# RodManipulator_SCH.net
KiCad netlist of a schematic drawn in Altium Designer
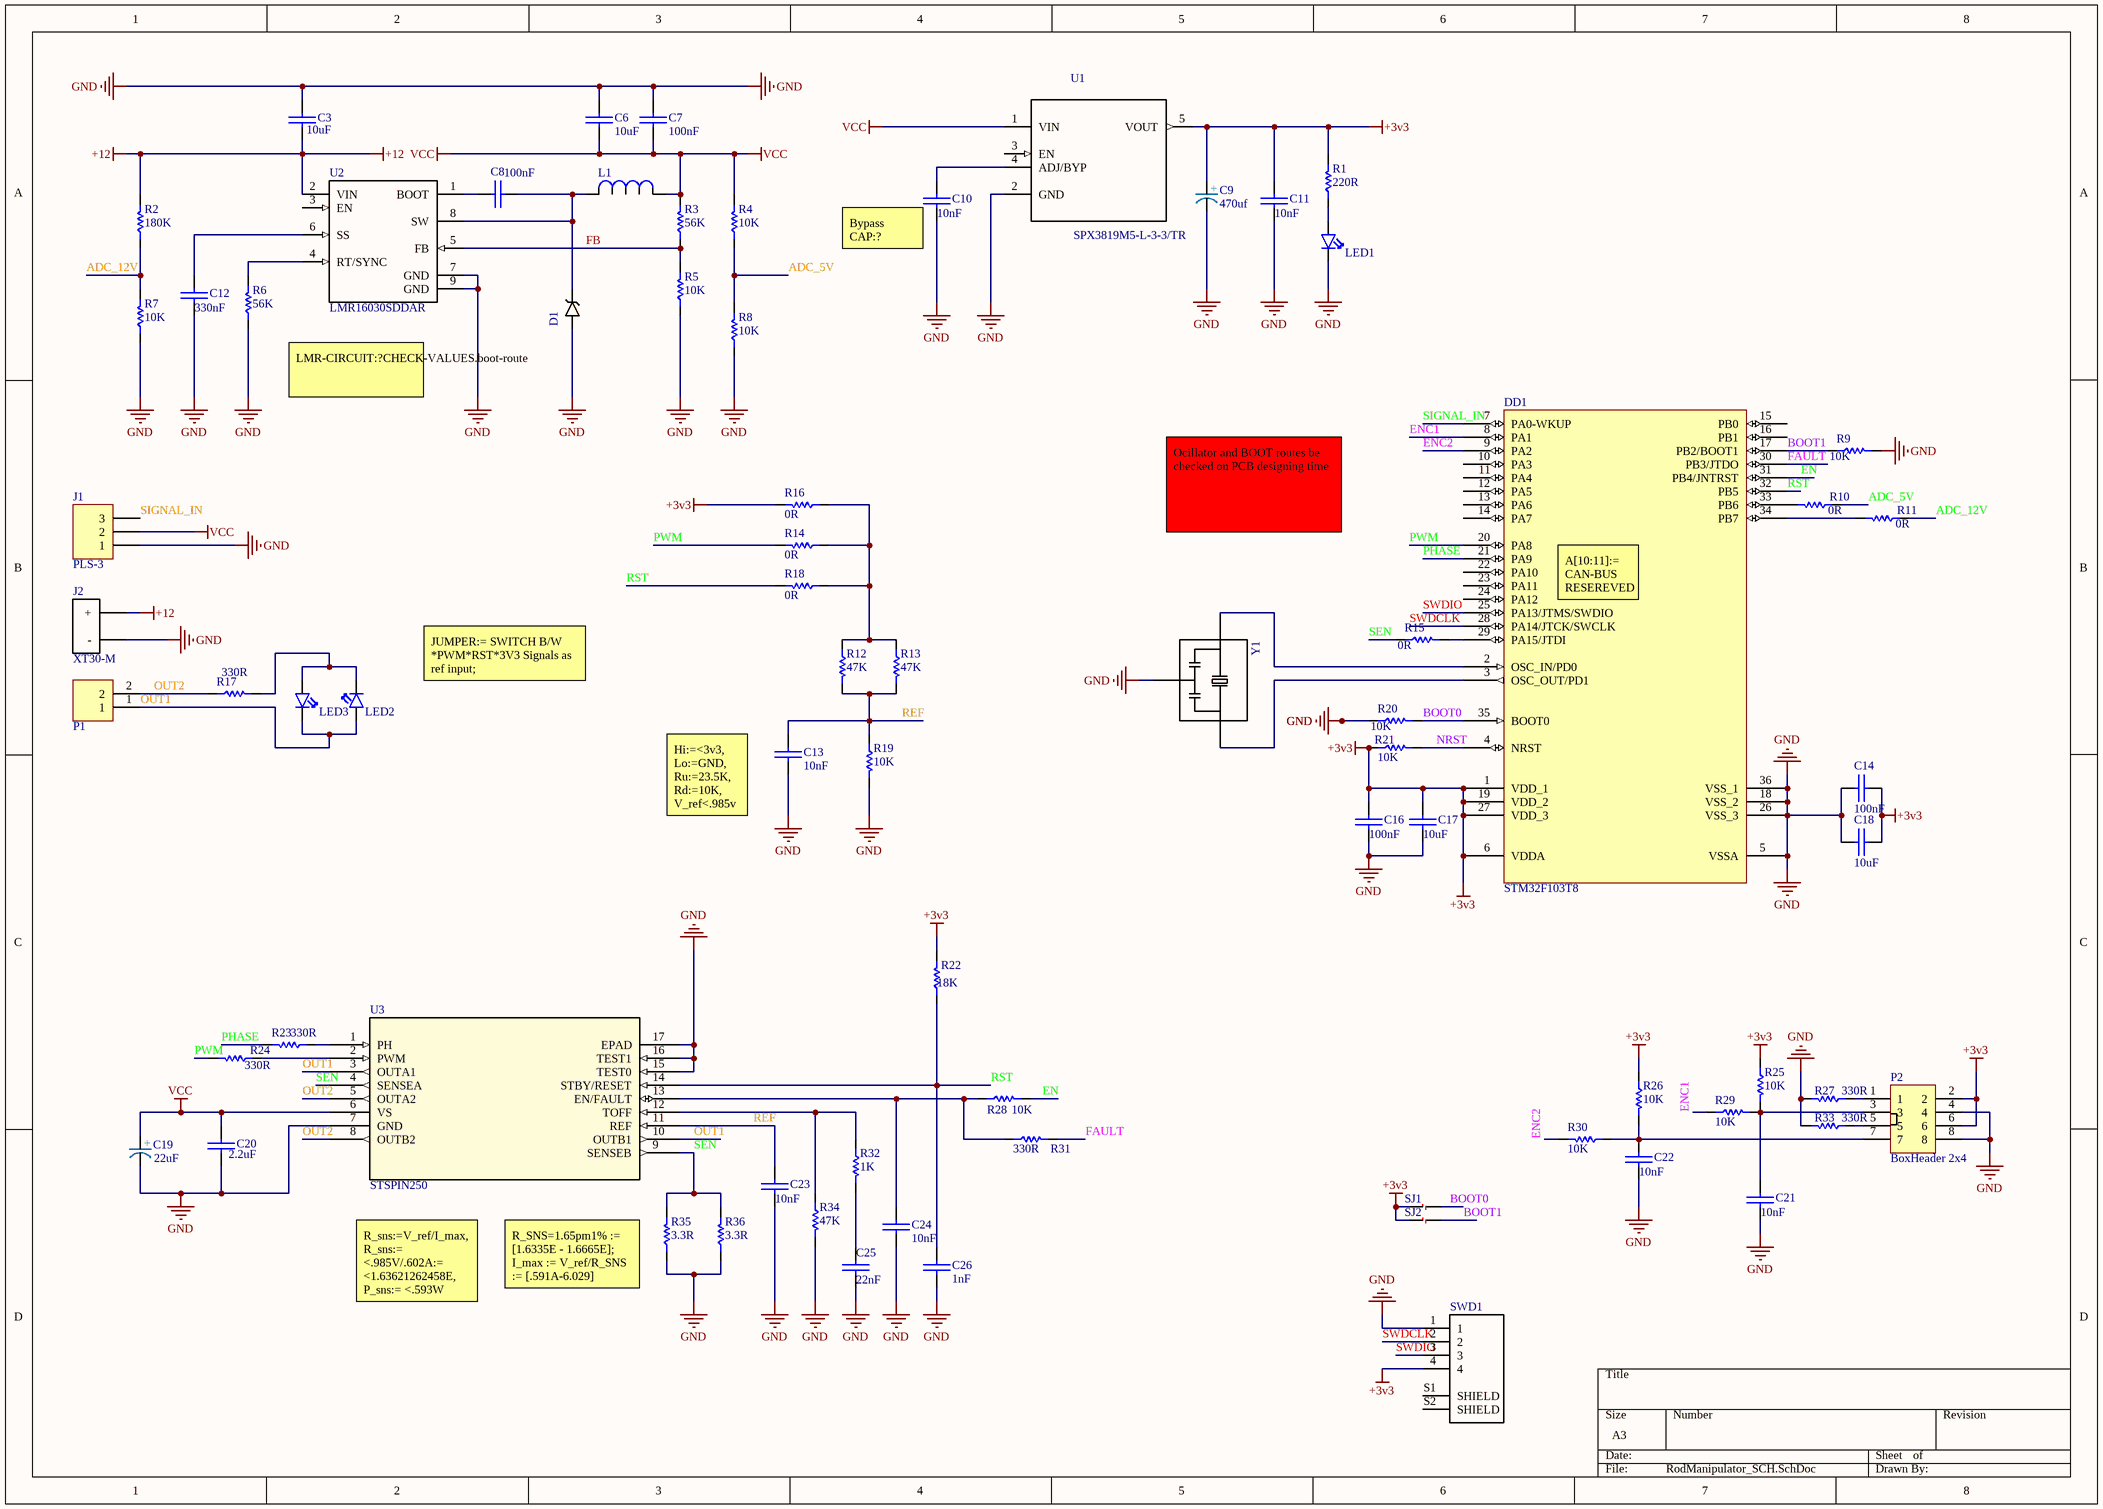
[diagram p0: RodManipulator_SCH.SchDoc]

(export (version "E")
  (design (tool "Eeschema 10.0.6"))
  (components
    (comp (ref "C3")
      (value "10uF")
      (footprint "SMD_CAP_0603")
      (description "Bipolar Capacitor")
      (fields (field (name "VOLTAGE") "100V") (field (name "DESIGNER") "Saeid Jorablo"))
      (libsource (lib "R2T Team Library") (part "Cap-Bipolar"))
    )
    (comp (ref "C6")
      (value "10uF")
      (footprint "SMD_CAP_0603")
      (description "Bipolar Capacitor")
      (fields (field (name "VOLTAGE") "100V") (field (name "DESIGNER") "Saeid Jorablo"))
      (libsource (lib "R2T Team Library") (part "Cap-Bipolar"))
    )
    (comp (ref "C7")
      (value "100nF")
      (footprint "SMD_CAP_0603")
      (description "Bipolar Capacitor")
      (fields (field (name "VOLTAGE") "100V") (field (name "DESIGNER") "Saeid Jorablo"))
      (libsource (lib "R2T Team Library") (part "Cap-Bipolar"))
    )
    (comp (ref "C8")
      (value "100nF")
      (footprint "SMD_CAP_0603")
      (description "Bipolar Capacitor")
      (fields (field (name "VOLTAGE") "100V") (field (name "DESIGNER") "Saeid Jorablo"))
      (libsource (lib "R2T Team Library") (part "Cap-Bipolar"))
    )
    (comp (ref "C9")
      (value "470uf")
      (footprint "Tantalum Cap Size A - 1206")
      (description "470uf,16v")
      (fields (field (name "DESIGNER") "Hamed Jafarzadeh ( R2T )"))
      (libsource (lib "") (part "Capacitor Polarized_1"))
    )
    (comp (ref "C10")
      (value "10nF")
      (footprint "SMD_CAP_0603")
      (description "Bipolar Capacitor")
      (fields (field (name "VOLTAGE") "100V") (field (name "DESIGNER") "Saeid Jorablo"))
      (libsource (lib "R2T Team Library") (part "Cap-Bipolar"))
    )
    (comp (ref "C11")
      (value "10nF")
      (footprint "SMD_CAP_0603")
      (description "Bipolar Capacitor")
      (fields (field (name "VOLTAGE") "100V") (field (name "DESIGNER") "Saeid Jorablo"))
      (libsource (lib "R2T Team Library") (part "Cap-Bipolar"))
    )
    (comp (ref "C12")
      (value "330nF")
      (footprint "SMD_CAP_0603")
      (description "Bipolar Capacitor")
      (fields (field (name "VOLTAGE") "100V") (field (name "DESIGNER") "Saeid Jorablo"))
      (libsource (lib "R2T Team Library") (part "Cap-Bipolar"))
    )
    (comp (ref "C13")
      (value "10nF")
      (footprint "SMD_CAP_0603")
      (description "Bipolar Capacitor")
      (fields (field (name "VOLTAGE") "100V") (field (name "DESIGNER") "Saeid Jorablo"))
      (libsource (lib "R2T Team Library") (part "Cap-Bipolar"))
    )
    (comp (ref "C14")
      (value "100nF")
      (footprint "SMD_CAP_0603")
      (description "Bipolar Capacitor")
      (fields (field (name "VOLTAGE") "100V") (field (name "DESIGNER") "Saeid Jorablo"))
      (libsource (lib "R2T Team Library") (part "Cap-Bipolar"))
    )
    (comp (ref "C16")
      (value "100nF")
      (footprint "SMD_CAP_0603")
      (description "Bipolar Capacitor")
      (fields (field (name "VOLTAGE") "100V") (field (name "DESIGNER") "Saeid Jorablo"))
      (libsource (lib "R2T Team Library") (part "Cap-Bipolar"))
    )
    (comp (ref "C17")
      (value "10uF")
      (footprint "SMD_CAP_0603")
      (description "Bipolar Capacitor")
      (fields (field (name "VOLTAGE") "100V") (field (name "DESIGNER") "Saeid Jorablo"))
      (libsource (lib "R2T Team Library") (part "Cap-Bipolar"))
    )
    (comp (ref "C18")
      (value "10uF")
      (footprint "SMD_CAP_0603")
      (description "Bipolar Capacitor")
      (fields (field (name "VOLTAGE") "100V") (field (name "DESIGNER") "Saeid Jorablo"))
      (libsource (lib "R2T Team Library") (part "Cap-Bipolar"))
    )
    (comp (ref "C19")
      (value "22uF")
      (footprint "Tantalum Cap Size A - 1206")
      (fields (field (name "DESIGNER") "Hamed Jafarzadeh ( R2T )"))
      (libsource (lib "R2T Team Library") (part "Capacitor Polarized"))
    )
    (comp (ref "C20")
      (value "2.2uF")
      (footprint "SMD_CAP_0603")
      (description "Bipolar Capacitor")
      (fields (field (name "VOLTAGE") "100V") (field (name "DESIGNER") "Saeid Jorablo"))
      (libsource (lib "R2T Team Library") (part "Cap-Bipolar"))
    )
    (comp (ref "C21")
      (value "10nF")
      (footprint "SMD_CAP_0603")
      (description "Bipolar Capacitor")
      (fields (field (name "VOLTAGE") "100V") (field (name "DESIGNER") "Saeid Jorablo"))
      (libsource (lib "R2T Team Library") (part "Cap-Bipolar"))
    )
    (comp (ref "C22")
      (value "10nF")
      (footprint "SMD_CAP_0603")
      (description "Bipolar Capacitor")
      (fields (field (name "VOLTAGE") "100V") (field (name "DESIGNER") "Saeid Jorablo"))
      (libsource (lib "R2T Team Library") (part "Cap-Bipolar"))
    )
    (comp (ref "C23")
      (value "10nF")
      (footprint "SMD_CAP_0603")
      (description "Bipolar Capacitor")
      (fields (field (name "VOLTAGE") "100V") (field (name "DESIGNER") "Saeid Jorablo"))
      (libsource (lib "R2T Team Library") (part "Cap-Bipolar"))
    )
    (comp (ref "C24")
      (value "10nF")
      (footprint "SMD_CAP_0603")
      (description "Bipolar Capacitor")
      (fields (field (name "VOLTAGE") "100V") (field (name "DESIGNER") "Saeid Jorablo"))
      (libsource (lib "R2T Team Library") (part "Cap-Bipolar"))
    )
    (comp (ref "C25")
      (value "22nF")
      (footprint "SMD_CAP_0603")
      (description "Bipolar Capacitor")
      (fields (field (name "VOLTAGE") "100V") (field (name "DESIGNER") "Saeid Jorablo"))
      (libsource (lib "R2T Team Library") (part "Cap-Bipolar"))
    )
    (comp (ref "C26")
      (value "1nF")
      (footprint "SMD_CAP_0603")
      (description "Bipolar Capacitor")
      (fields (field (name "VOLTAGE") "100V") (field (name "DESIGNER") "Saeid Jorablo"))
      (libsource (lib "R2T Team Library") (part "Cap-Bipolar"))
    )
    (comp (ref "D1")
      (value "SK56")
      (footprint "*SMB_P6SMB62AT3G(Primary)")
      (description "Диод Шоттки 5А 60В [SMB / DO-214AA]")
      (fields (field (name "MF") "Littelfuse Inc."))
      (libsource (lib "lib") (part "SK56"))
    )
    (comp (ref "DD1")
      (value "STM32F103T8")
      (footprint "*QFN50P600X600X100-37N")
      (description "STM32F103T8U6, Микроконтроллер 32BIT ARM 64K FLASH [VFQFPN-36]")
      (fields (field (name "MF") "STM") (field (name "MP") "STM32F103T8U6"))
      (libsource (lib "lib") (part "STM32F103T8"))
    )
    (comp (ref "J1")
      (value "PLS-3")
      (footprint "HDR Side 3 pin")
      (description "Header, 3-Pin")
      (fields (field (name "MF") "Connfly electronic (Zhenqin)") (field (name "MP") "PLS-3 (DS1021-1x3)"))
      (libsource (lib "lib") (part "PLS-3"))
    )
    (comp (ref "J2")
      (value "XT30-M")
      (footprint "XT30-M")
      (fields (field (name "MP") "XT60-M") (field (name "MF") "AMASS"))
      (libsource (lib "lib") (part "XT30-M"))
    )
    (comp (ref "L1")
      (value "IHLP2020BZER100M01")
      (footprint "IHLP")
      (description "10µH Shielded Molded Inductor 2.3A 199mOhm Max Nonstandard")
      (fields (field (name "MF") "Vishay Dale"))
      (libsource (lib "lib") (part "IHLP2020BZER100M01"))
    )
    (comp (ref "LED1")
      (value "LED")
      (footprint "LED0603")
      (fields (field (name "DESIGNER :") "Razi Research Team Of Mashhad - Hamed Jafarzadeh"))
      (libsource (lib "R2T Team Library") (part "LED"))
    )
    (comp (ref "LED2")
      (value "LED")
      (footprint "LED0603")
      (fields (field (name "DESIGNER :") "Razi Research Team Of Mashhad - Hamed Jafarzadeh"))
      (libsource (lib "R2T Team Library") (part "LED"))
    )
    (comp (ref "LED3")
      (value "LED")
      (footprint "LED0603")
      (fields (field (name "DESIGNER :") "Razi Research Team Of Mashhad - Hamed Jafarzadeh"))
      (libsource (lib "R2T Team Library") (part "LED"))
    )
    (comp (ref "P1")
      (value "Connector")
      (footprint "PH Connector 2Pin")
      (fields (field (name "DESIGNER:") "Hamed Jafarzadeh - www.R2T.ir"))
      (libsource (lib "R2T Team Library") (part "Connector 2Pin"))
    )
    (comp (ref "P2")
      (value "BoxHeader 2x4")
      (footprint "Box Header 2x4")
      (fields (field (name "DESIGNER") "HamedJafarzadeh - ww.R2T.ir"))
      (libsource (lib "R2T Team Library") (part "BoxHeader 2x4"))
    )
    (comp (ref "R1")
      (value "220R")
      (footprint "RES 0603 (1608X06L)")
      (description "Resistor")
      (fields (field (name "TOLERANCE") "5%") (field (name "POWER") "1/8 W"))
      (libsource (lib "R2T Team Library") (part "Resistor"))
    )
    (comp (ref "R2")
      (value "180K")
      (footprint "RES 0603 (1608X06L)")
      (description "Resistor")
      (fields (field (name "TOLERANCE") "5%") (field (name "POWER") "1/8 W"))
      (libsource (lib "R2T Team Library") (part "Resistor"))
    )
    (comp (ref "R3")
      (value "56K")
      (footprint "RES 0603 (1608X06L)")
      (description "Resistor")
      (fields (field (name "TOLERANCE") "5%") (field (name "POWER") "1/8 W"))
      (libsource (lib "R2T Team Library") (part "Resistor"))
    )
    (comp (ref "R4")
      (value "10K")
      (footprint "RES 0603 (1608X06L)")
      (description "Resistor")
      (fields (field (name "TOLERANCE") "5%") (field (name "POWER") "1/8 W"))
      (libsource (lib "R2T Team Library") (part "Resistor"))
    )
    (comp (ref "R5")
      (value "10K")
      (footprint "RES 0603 (1608X06L)")
      (description "Resistor")
      (fields (field (name "TOLERANCE") "5%") (field (name "POWER") "1/8 W"))
      (libsource (lib "R2T Team Library") (part "Resistor"))
    )
    (comp (ref "R6")
      (value "56K")
      (footprint "RES 0603 (1608X06L)")
      (description "Resistor")
      (fields (field (name "TOLERANCE") "5%") (field (name "POWER") "1/8 W"))
      (libsource (lib "R2T Team Library") (part "Resistor"))
    )
    (comp (ref "R7")
      (value "10K")
      (footprint "RES 0603 (1608X06L)")
      (description "Resistor")
      (fields (field (name "TOLERANCE") "5%") (field (name "POWER") "1/8 W"))
      (libsource (lib "R2T Team Library") (part "Resistor"))
    )
    (comp (ref "R8")
      (value "10K")
      (footprint "RES 0603 (1608X06L)")
      (description "Resistor")
      (fields (field (name "TOLERANCE") "5%") (field (name "POWER") "1/8 W"))
      (libsource (lib "R2T Team Library") (part "Resistor"))
    )
    (comp (ref "R9")
      (value "10K")
      (footprint "RES 0603 (1608X06L)")
      (description "Resistor")
      (fields (field (name "TOLERANCE") "5%") (field (name "POWER") "1/8 W"))
      (libsource (lib "R2T Team Library") (part "Resistor"))
    )
    (comp (ref "R10")
      (value "0R")
      (footprint "RES 0603 (1608X06L)")
      (description "Resistor")
      (fields (field (name "TOLERANCE") "5%") (field (name "POWER") "1/8 W"))
      (libsource (lib "R2T Team Library") (part "Resistor"))
    )
    (comp (ref "R11")
      (value "0R")
      (footprint "RES 0603 (1608X06L)")
      (description "Resistor")
      (fields (field (name "TOLERANCE") "5%") (field (name "POWER") "1/8 W"))
      (libsource (lib "R2T Team Library") (part "Resistor"))
    )
    (comp (ref "R12")
      (value "47K")
      (footprint "RES 0603 (1608X06L)")
      (description "Resistor")
      (fields (field (name "TOLERANCE") "5%") (field (name "POWER") "1/8 W"))
      (libsource (lib "R2T Team Library") (part "Resistor"))
    )
    (comp (ref "R13")
      (value "47K")
      (footprint "RES 0603 (1608X06L)")
      (description "Resistor")
      (fields (field (name "TOLERANCE") "5%") (field (name "POWER") "1/8 W"))
      (libsource (lib "R2T Team Library") (part "Resistor"))
    )
    (comp (ref "R14")
      (value "0R")
      (footprint "RES 0603 (1608X06L)")
      (description "Resistor")
      (fields (field (name "TOLERANCE") "5%") (field (name "POWER") "1/8 W"))
      (libsource (lib "R2T Team Library") (part "Resistor"))
    )
    (comp (ref "R15")
      (value "0R")
      (footprint "RES 0603 (1608X06L)")
      (description "Resistor")
      (fields (field (name "TOLERANCE") "5%") (field (name "POWER") "1/8 W"))
      (libsource (lib "R2T Team Library") (part "Resistor"))
    )
    (comp (ref "R16")
      (value "0R")
      (footprint "RES 0603 (1608X06L)")
      (description "Resistor")
      (fields (field (name "TOLERANCE") "5%") (field (name "POWER") "1/8 W"))
      (libsource (lib "R2T Team Library") (part "Resistor"))
    )
    (comp (ref "R17")
      (value "330R")
      (footprint "RES 0603 (1608X06L)")
      (description "Resistor")
      (fields (field (name "TOLERANCE") "5%") (field (name "POWER") "1/8 W"))
      (libsource (lib "R2T Team Library") (part "Resistor"))
    )
    (comp (ref "R18")
      (value "0R")
      (footprint "RES 0603 (1608X06L)")
      (description "Resistor")
      (fields (field (name "TOLERANCE") "5%") (field (name "POWER") "1/8 W"))
      (libsource (lib "R2T Team Library") (part "Resistor"))
    )
    (comp (ref "R19")
      (value "10K")
      (footprint "RES 0603 (1608X06L)")
      (description "Resistor")
      (fields (field (name "TOLERANCE") "5%") (field (name "POWER") "1/8 W"))
      (libsource (lib "R2T Team Library") (part "Resistor"))
    )
    (comp (ref "R20")
      (value "10K")
      (footprint "RES 0603 (1608X06L)")
      (description "Resistor")
      (fields (field (name "TOLERANCE") "5%") (field (name "POWER") "1/8 W"))
      (libsource (lib "R2T Team Library") (part "Resistor"))
    )
    (comp (ref "R21")
      (value "10K")
      (footprint "RES 0603 (1608X06L)")
      (description "Resistor")
      (fields (field (name "TOLERANCE") "5%") (field (name "POWER") "1/8 W"))
      (libsource (lib "R2T Team Library") (part "Resistor"))
    )
    (comp (ref "R22")
      (value "18K")
      (footprint "RES 0603 (1608X06L)")
      (description "Resistor")
      (fields (field (name "TOLERANCE") "5%") (field (name "POWER") "1/8 W"))
      (libsource (lib "R2T Team Library") (part "Resistor"))
    )
    (comp (ref "R23")
      (value "330R")
      (footprint "RES 0603 (1608X06L)")
      (description "Resistor")
      (fields (field (name "TOLERANCE") "5%") (field (name "POWER") "1/8 W"))
      (libsource (lib "R2T Team Library") (part "Resistor"))
    )
    (comp (ref "R24")
      (value "330R")
      (footprint "RES 0603 (1608X06L)")
      (description "Resistor")
      (fields (field (name "TOLERANCE") "5%") (field (name "POWER") "1/8 W"))
      (libsource (lib "R2T Team Library") (part "Resistor"))
    )
    (comp (ref "R25")
      (value "10K")
      (footprint "RES 0603 (1608X06L)")
      (description "Resistor")
      (fields (field (name "TOLERANCE") "5%") (field (name "POWER") "1/8 W"))
      (libsource (lib "R2T Team Library") (part "Resistor"))
    )
    (comp (ref "R26")
      (value "10K")
      (footprint "RES 0603 (1608X06L)")
      (description "Resistor")
      (fields (field (name "TOLERANCE") "5%") (field (name "POWER") "1/8 W"))
      (libsource (lib "R2T Team Library") (part "Resistor"))
    )
    (comp (ref "R27")
      (value "330R")
      (footprint "RES 0603 (1608X06L)")
      (description "Resistor")
      (fields (field (name "TOLERANCE") "5%") (field (name "POWER") "1/8 W"))
      (libsource (lib "R2T Team Library") (part "Resistor"))
    )
    (comp (ref "R28")
      (value "10K")
      (footprint "RES 0603 (1608X06L)")
      (description "Resistor")
      (fields (field (name "TOLERANCE") "5%") (field (name "POWER") "1/8 W"))
      (libsource (lib "R2T Team Library") (part "Resistor"))
    )
    (comp (ref "R29")
      (value "10K")
      (footprint "RES 0603 (1608X06L)")
      (description "Resistor")
      (fields (field (name "TOLERANCE") "5%") (field (name "POWER") "1/8 W"))
      (libsource (lib "R2T Team Library") (part "Resistor"))
    )
    (comp (ref "R30")
      (value "10K")
      (footprint "RES 0603 (1608X06L)")
      (description "Resistor")
      (fields (field (name "TOLERANCE") "5%") (field (name "POWER") "1/8 W"))
      (libsource (lib "R2T Team Library") (part "Resistor"))
    )
    (comp (ref "R31")
      (value "330R")
      (footprint "RES 0603 (1608X06L)")
      (description "Resistor")
      (fields (field (name "TOLERANCE") "5%") (field (name "POWER") "1/8 W"))
      (libsource (lib "R2T Team Library") (part "Resistor"))
    )
    (comp (ref "R32")
      (value "1K")
      (footprint "RES 0603 (1608X06L)")
      (description "Resistor")
      (fields (field (name "TOLERANCE") "5%") (field (name "POWER") "1/8 W"))
      (libsource (lib "R2T Team Library") (part "Resistor"))
    )
    (comp (ref "R33")
      (value "330R")
      (footprint "RES 0603 (1608X06L)")
      (description "Resistor")
      (fields (field (name "TOLERANCE") "5%") (field (name "POWER") "1/8 W"))
      (libsource (lib "R2T Team Library") (part "Resistor"))
    )
    (comp (ref "R34")
      (value "47K")
      (footprint "RES 0603 (1608X06L)")
      (description "Resistor")
      (fields (field (name "TOLERANCE") "5%") (field (name "POWER") "1/8 W"))
      (libsource (lib "R2T Team Library") (part "Resistor"))
    )
    (comp (ref "R35")
      (value "3.3R")
      (footprint "RES 2010 (5026X08L)")
      (description "Resistor")
      (fields (field (name "TOLERANCE") "5%") (field (name "POWER") "1/8 W"))
      (libsource (lib "R2T Team Library") (part "Resistor"))
    )
    (comp (ref "R36")
      (value "3.3R")
      (footprint "RES 2010 (5026X08L)")
      (description "Resistor")
      (fields (field (name "TOLERANCE") "5%") (field (name "POWER") "1/8 W"))
      (libsource (lib "R2T Team Library") (part "Resistor"))
    )
    (comp (ref "SJ1")
      (value "SmdJumper")
      (footprint "RES 0603 (1608X06L)")
      (libsource (lib "R2T Team Library") (part "SmdJumper"))
    )
    (comp (ref "SJ2")
      (value "SmdJumper")
      (footprint "RES 0603 (1608X06L)")
      (libsource (lib "R2T Team Library") (part "SmdJumper"))
    )
    (comp (ref "SWD1")
      (value "SM04B-GHS-TB(LF)(SN)-")
      (footprint "JST_BM04B-GHS-holes")
      (description "Conn Shrouded Header HDR 4 POS 1.25mm Solder ST SMD Reel")
      (fields (field (name "MF") "JST Sales") (field (name "MP") "SM04B-GHS-TB(LF)(SN)"))
      (libsource (lib "lib") (part "SWD SM04B-GHS-TB(LF)(SN)-"))
    )
    (comp (ref "U1")
      (value "SPX3819M5-L-3-3/TR")
      (footprint "*SOT95P280X145-5N")
      (description "Low Dropout Voltage Regulator, Adjustable 0.5A, В±1%, 2.5 to 16 Vin, 5-Pin SOT-23")
      (fields (field (name "MF") "MaxLinear, Inc."))
      (libsource (lib "lib") (part "SPX3819M5-L-3-3/TR"))
    )
    (comp (ref "U2")
      (value "LMR16030SDDAR")
      (footprint "*SOIC127P600X170-9N - duplicate")
      (fields (field (name "MF") "Texas Instruments"))
      (libsource (lib "lib") (part "LMR16030SDDAR"))
    )
    (comp (ref "U3")
      (value "STSPIN250")
      (footprint "VFQFPN-16")
      (description "No Description Available")
      (fields
        (field (name "MANUFACTURER_PART_NUMBER") "STSPIN220")
        (field (name "COPYRIGHT") "Copyright (C) 2018 Accelerated Designs. All rights reserved")
      )
      (libsource (lib "lib") (part "STSPIN250"))
    )
    (comp (ref "Y1")
      (value "CSTCE8M00G55-R0")
      (footprint "*OSC_CSTCE8M00G55-R0")
      (description "Ceramic Resonator 8MHz ??0.5% _Tol_ ??0.2% _Stability_ 33pF 40Ohm 3-Pin CSMD T/R")
      (fields (field (name "MF") "Murata"))
      (libsource (lib "lib") (part "CSTCE8M00G55-R0"))
    )
  )
  (nets
    (net (code "1") (name "+3v3") (class "Default")
      (node (ref "C11") (pin "2") (pinfunction "-_2") (pintype "passive"))
      (node (ref "C14") (pin "1") (pinfunction "+_1") (pintype "passive"))
      (node (ref "C16") (pin "1") (pinfunction "+_1") (pintype "passive"))
      (node (ref "C17") (pin "1") (pinfunction "+_1") (pintype "passive"))
      (node (ref "C18") (pin "1") (pinfunction "+_1") (pintype "passive"))
      (node (ref "C9") (pin "1") (pintype "passive"))
      (node (ref "DD1") (pin "1") (pinfunction "VDD_1_1") (pintype "power_in"))
      (node (ref "DD1") (pin "19") (pinfunction "VDD_2_19") (pintype "power_in"))
      (node (ref "DD1") (pin "27") (pinfunction "VDD_3_27") (pintype "power_in"))
      (node (ref "DD1") (pin "6") (pinfunction "VDDA_6") (pintype "power_in"))
      (node (ref "P2") (pin "2") (pinfunction "2_2") (pintype "passive"))
      (node (ref "P2") (pin "6") (pinfunction "6_6") (pintype "passive"))
      (node (ref "R1") (pin "2") (pinfunction "2_2") (pintype "passive"))
      (node (ref "R16") (pin "2") (pinfunction "2_2") (pintype "passive"))
      (node (ref "R21") (pin "1") (pinfunction "1_1") (pintype "passive"))
      (node (ref "R22") (pin "2") (pinfunction "2_2") (pintype "passive"))
      (node (ref "R25") (pin "1") (pinfunction "1_1") (pintype "passive"))
      (node (ref "R26") (pin "1") (pinfunction "1_1") (pintype "passive"))
      (node (ref "SJ1") (pin "2") (pinfunction "2_2") (pintype "passive"))
      (node (ref "SJ2") (pin "2") (pinfunction "2_2") (pintype "passive"))
      (node (ref "SWD1") (pin "4") (pinfunction "4_4") (pintype "passive"))
      (node (ref "U1") (pin "5") (pinfunction "VOUT_5") (pintype "output"))
    )
    (net (code "2") (name "+12") (class "Default")
      (node (ref "C3") (pin "1") (pinfunction "+_1") (pintype "passive"))
      (node (ref "J2") (pin "PLUS") (pinfunction "+_PLUS") (pintype "passive"))
      (node (ref "R2") (pin "2") (pinfunction "2_2") (pintype "passive"))
      (node (ref "U2") (pin "2") (pinfunction "VIN_2") (pintype "power_in"))
    )
    (net (code "3") (name "/ADC_5V") (class "Default")
      (node (ref "R10") (pin "1") (pinfunction "1_1") (pintype "passive"))
      (node (ref "R4") (pin "1") (pinfunction "1_1") (pintype "passive"))
      (node (ref "R8") (pin "2") (pinfunction "2_2") (pintype "passive"))
    )
    (net (code "4") (name "/ADC_12V") (class "Default")
      (node (ref "R11") (pin "1") (pinfunction "1_1") (pintype "passive"))
      (node (ref "R2") (pin "1") (pinfunction "1_1") (pintype "passive"))
      (node (ref "R7") (pin "2") (pinfunction "2_2") (pintype "passive"))
    )
    (net (code "5") (name "/BOOT0") (class "Default")
      (node (ref "DD1") (pin "35") (pinfunction "BOOT0_35") (pintype "input"))
      (node (ref "R20") (pin "2") (pinfunction "2_2") (pintype "passive"))
      (node (ref "SJ1") (pin "1") (pintype "passive"))
    )
    (net (code "6") (name "/BOOT1") (class "Default")
      (node (ref "DD1") (pin "17") (pinfunction "PB2/BOOT1_17") (pintype "bidirectional"))
      (node (ref "R9") (pin "1") (pinfunction "1_1") (pintype "passive"))
      (node (ref "SJ2") (pin "1") (pintype "passive"))
    )
    (net (code "7") (name "/EN") (class "Default")
      (node (ref "DD1") (pin "31") (pinfunction "PB4/JNTRST_31") (pintype "bidirectional"))
      (node (ref "R28") (pin "2") (pinfunction "2_2") (pintype "passive"))
    )
    (net (code "8") (name "/ENC1") (class "Default")
      (node (ref "DD1") (pin "8") (pinfunction "PA1_8") (pintype "bidirectional"))
      (node (ref "R29") (pin "1") (pinfunction "1_1") (pintype "passive"))
    )
    (net (code "9") (name "/ENC2") (class "Default")
      (node (ref "DD1") (pin "9") (pinfunction "PA2_9") (pintype "bidirectional"))
      (node (ref "R30") (pin "2") (pinfunction "2_2") (pintype "passive"))
    )
    (net (code "10") (name "/FAULT") (class "Default")
      (node (ref "DD1") (pin "30") (pinfunction "PB3/JTDO_30") (pintype "bidirectional"))
      (node (ref "R31") (pin "2") (pinfunction "2_2") (pintype "passive"))
    )
    (net (code "11") (name "/FB") (class "Default")
      (node (ref "R3") (pin "1") (pinfunction "1_1") (pintype "passive"))
      (node (ref "R5") (pin "2") (pinfunction "2_2") (pintype "passive"))
      (node (ref "U2") (pin "5") (pinfunction "FB_5") (pintype "input"))
    )
    (net (code "12") (name "/NRST") (class "Default")
      (node (ref "DD1") (pin "4") (pinfunction "NRST_4") (pintype "bidirectional"))
      (node (ref "R21") (pin "2") (pinfunction "2_2") (pintype "passive"))
    )
    (net (code "13") (name "/OUT1") (class "Default")
      (node (ref "LED2") (pin "1") (pinfunction "A_1") (pintype "passive"))
      (node (ref "LED3") (pin "2") (pinfunction "K_2") (pintype "passive"))
      (node (ref "P1") (pin "1") (pinfunction "1_1") (pintype "passive"))
      (node (ref "U3") (pin "10") (pinfunction "OUTB1_10") (pintype "output"))
      (node (ref "U3") (pin "3") (pinfunction "OUTA1_3") (pintype "output"))
    )
    (net (code "14") (name "/OUT2") (class "Default")
      (node (ref "P1") (pin "2") (pinfunction "2_2") (pintype "passive"))
      (node (ref "R17") (pin "1") (pinfunction "1_1") (pintype "passive"))
      (node (ref "U3") (pin "5") (pinfunction "OUTA2_5") (pintype "output"))
      (node (ref "U3") (pin "8") (pinfunction "OUTB2_8") (pintype "output"))
    )
    (net (code "15") (name "/PHASE") (class "Default")
      (node (ref "DD1") (pin "21") (pinfunction "PA9_21") (pintype "bidirectional"))
      (node (ref "R23") (pin "2") (pinfunction "2_2") (pintype "passive"))
    )
    (net (code "16") (name "/PWM") (class "Default")
      (node (ref "DD1") (pin "20") (pinfunction "PA8_20") (pintype "bidirectional"))
      (node (ref "R14") (pin "2") (pinfunction "2_2") (pintype "passive"))
      (node (ref "R24") (pin "2") (pinfunction "2_2") (pintype "passive"))
    )
    (net (code "17") (name "/REF") (class "Default")
      (node (ref "C13") (pin "2") (pinfunction "-_2") (pintype "passive"))
      (node (ref "C23") (pin "1") (pinfunction "+_1") (pintype "passive"))
      (node (ref "R12") (pin "2") (pinfunction "2_2") (pintype "passive"))
      (node (ref "R13") (pin "2") (pinfunction "2_2") (pintype "passive"))
      (node (ref "R19") (pin "1") (pinfunction "1_1") (pintype "passive"))
      (node (ref "U3") (pin "11") (pinfunction "REF_11") (pintype "input"))
    )
    (net (code "18") (name "/RST") (class "Default")
      (node (ref "C26") (pin "2") (pinfunction "-_2") (pintype "passive"))
      (node (ref "DD1") (pin "32") (pinfunction "PB5_32") (pintype "bidirectional"))
      (node (ref "R18") (pin "2") (pinfunction "2_2") (pintype "passive"))
      (node (ref "R22") (pin "1") (pinfunction "1_1") (pintype "passive"))
      (node (ref "U3") (pin "14") (pinfunction "STBY/RESET_14") (pintype "input"))
    )
    (net (code "19") (name "/SEN") (class "Default")
      (node (ref "R15") (pin "1") (pinfunction "1_1") (pintype "passive"))
      (node (ref "R35") (pin "2") (pinfunction "2_2") (pintype "passive"))
      (node (ref "R36") (pin "2") (pinfunction "2_2") (pintype "passive"))
      (node (ref "U3") (pin "4") (pinfunction "SENSEA_4") (pintype "output"))
      (node (ref "U3") (pin "9") (pinfunction "SENSEB_9") (pintype "output"))
    )
    (net (code "20") (name "/SIGNAL_IN") (class "Default")
      (node (ref "DD1") (pin "7") (pinfunction "PA0-WKUP_7") (pintype "bidirectional"))
      (node (ref "J1") (pin "3") (pinfunction "3_3") (pintype "passive"))
    )
    (net (code "21") (name "/SWDCLK") (class "Default")
      (node (ref "DD1") (pin "28") (pinfunction "PA14/JTCK/SWCLK_28") (pintype "bidirectional"))
      (node (ref "SWD1") (pin "2") (pinfunction "2_2") (pintype "passive"))
    )
    (net (code "22") (name "/SWDIO") (class "Default")
      (node (ref "DD1") (pin "25") (pinfunction "PA13/JTMS/SWDIO_25") (pintype "bidirectional"))
      (node (ref "SWD1") (pin "3") (pinfunction "3_3") (pintype "passive"))
    )
    (net (code "23") (name "GND") (class "Default")
      (node (ref "C10") (pin "1") (pinfunction "+_1") (pintype "passive"))
      (node (ref "C11") (pin "1") (pinfunction "+_1") (pintype "passive"))
      (node (ref "C12") (pin "2") (pinfunction "-_2") (pintype "passive"))
      (node (ref "C13") (pin "1") (pinfunction "+_1") (pintype "passive"))
      (node (ref "C14") (pin "2") (pinfunction "-_2") (pintype "passive"))
      (node (ref "C16") (pin "2") (pinfunction "-_2") (pintype "passive"))
      (node (ref "C17") (pin "2") (pinfunction "-_2") (pintype "passive"))
      (node (ref "C18") (pin "2") (pinfunction "-_2") (pintype "passive"))
      (node (ref "C19") (pin "2") (pintype "passive"))
      (node (ref "C20") (pin "2") (pinfunction "-_2") (pintype "passive"))
      (node (ref "C21") (pin "1") (pinfunction "+_1") (pintype "passive"))
      (node (ref "C22") (pin "1") (pinfunction "+_1") (pintype "passive"))
      (node (ref "C23") (pin "2") (pinfunction "-_2") (pintype "passive"))
      (node (ref "C24") (pin "1") (pinfunction "+_1") (pintype "passive"))
      (node (ref "C25") (pin "2") (pinfunction "-_2") (pintype "passive"))
      (node (ref "C26") (pin "1") (pinfunction "+_1") (pintype "passive"))
      (node (ref "C3") (pin "2") (pinfunction "-_2") (pintype "passive"))
      (node (ref "C6") (pin "1") (pinfunction "+_1") (pintype "passive"))
      (node (ref "C7") (pin "2") (pinfunction "-_2") (pintype "passive"))
      (node (ref "C9") (pin "2") (pintype "passive"))
      (node (ref "D1") (pin "A") (pinfunction "A_A") (pintype "power_in"))
      (node (ref "DD1") (pin "18") (pinfunction "VSS_2_18") (pintype "power_in"))
      (node (ref "DD1") (pin "26") (pinfunction "VSS_3_26") (pintype "power_in"))
      (node (ref "DD1") (pin "36") (pinfunction "VSS_1_36") (pintype "power_in"))
      (node (ref "DD1") (pin "5") (pinfunction "VSSA_5") (pintype "power_in"))
      (node (ref "J1") (pin "1") (pinfunction "1_1") (pintype "passive"))
      (node (ref "J2") (pin "MINUS") (pinfunction "-_MINUS") (pintype "passive"))
      (node (ref "LED1") (pin "2") (pinfunction "K_2") (pintype "passive"))
      (node (ref "P2") (pin "4") (pinfunction "4_4") (pintype "passive"))
      (node (ref "P2") (pin "8") (pinfunction "8_8") (pintype "passive"))
      (node (ref "R19") (pin "2") (pinfunction "2_2") (pintype "passive"))
      (node (ref "R20") (pin "1") (pinfunction "1_1") (pintype "passive"))
      (node (ref "R27") (pin "2") (pinfunction "2_2") (pintype "passive"))
      (node (ref "R33") (pin "2") (pinfunction "2_2") (pintype "passive"))
      (node (ref "R34") (pin "2") (pinfunction "2_2") (pintype "passive"))
      (node (ref "R35") (pin "1") (pinfunction "1_1") (pintype "passive"))
      (node (ref "R36") (pin "1") (pinfunction "1_1") (pintype "passive"))
      (node (ref "R5") (pin "1") (pinfunction "1_1") (pintype "passive"))
      (node (ref "R6") (pin "1") (pinfunction "1_1") (pintype "passive"))
      (node (ref "R7") (pin "1") (pinfunction "1_1") (pintype "passive"))
      (node (ref "R8") (pin "1") (pinfunction "1_1") (pintype "passive"))
      (node (ref "R9") (pin "2") (pinfunction "2_2") (pintype "passive"))
      (node (ref "SWD1") (pin "1") (pinfunction "1_1") (pintype "passive"))
      (node (ref "U1") (pin "2") (pinfunction "GND_2") (pintype "passive"))
      (node (ref "U2") (pin "7") (pinfunction "GND_7") (pintype "power_in"))
      (node (ref "U2") (pin "9") (pinfunction "GND_9") (pintype "power_in"))
      (node (ref "U3") (pin "15") (pinfunction "TEST0_15") (pintype "input"))
      (node (ref "U3") (pin "16") (pinfunction "TEST1_16") (pintype "input"))
      (node (ref "U3") (pin "17") (pinfunction "EPAD_17") (pintype "passive"))
      (node (ref "U3") (pin "7") (pinfunction "GND_7") (pintype "power_in"))
      (node (ref "Y1") (pin "2") (pinfunction "2_2") (pintype "power_in"))
    )
    (net (code "24") (name "Net-(C8-+)") (class "Default")
      (node (ref "C8") (pin "1") (pinfunction "+_1") (pintype "passive"))
      (node (ref "D1") (pin "C") (pinfunction "C_C") (pintype "power_in"))
      (node (ref "L1") (pin "2") (pinfunction "2_2") (pintype "passive"))
      (node (ref "U2") (pin "8") (pinfunction "SW_8") (pintype "power_in"))
    )
    (net (code "25") (name "Net-(C8--)") (class "Default")
      (node (ref "C8") (pin "2") (pinfunction "-_2") (pintype "passive"))
      (node (ref "U2") (pin "1") (pinfunction "BOOT_1") (pintype "power_in"))
    )
    (net (code "26") (name "Net-(C10--)") (class "Default")
      (node (ref "C10") (pin "2") (pinfunction "-_2") (pintype "passive"))
      (node (ref "U1") (pin "4") (pinfunction "ADJ/BYP_4") (pintype "passive"))
    )
    (net (code "27") (name "Net-(C12-+)") (class "Default")
      (node (ref "C12") (pin "1") (pinfunction "+_1") (pintype "passive"))
      (node (ref "U2") (pin "6") (pinfunction "SS_6") (pintype "input"))
    )
    (net (code "28") (name "Net-(C21--)") (class "Default")
      (node (ref "C21") (pin "2") (pinfunction "-_2") (pintype "passive"))
      (node (ref "P2") (pin "3") (pinfunction "3_3") (pintype "passive"))
      (node (ref "R25") (pin "2") (pinfunction "2_2") (pintype "passive"))
      (node (ref "R29") (pin "2") (pinfunction "2_2") (pintype "passive"))
    )
    (net (code "29") (name "Net-(C22--)") (class "Default")
      (node (ref "C22") (pin "2") (pinfunction "-_2") (pintype "passive"))
      (node (ref "P2") (pin "7") (pinfunction "7_7") (pintype "passive"))
      (node (ref "R26") (pin "2") (pinfunction "2_2") (pintype "passive"))
      (node (ref "R30") (pin "1") (pinfunction "1_1") (pintype "passive"))
    )
    (net (code "30") (name "Net-(C24--)") (class "Default")
      (node (ref "C24") (pin "2") (pinfunction "-_2") (pintype "passive"))
      (node (ref "R28") (pin "1") (pinfunction "1_1") (pintype "passive"))
      (node (ref "R31") (pin "1") (pinfunction "1_1") (pintype "passive"))
      (node (ref "U3") (pin "13") (pinfunction "EN/FAULT_13") (pintype "bidirectional"))
    )
    (net (code "31") (name "Net-(C25-+)") (class "Default")
      (node (ref "C25") (pin "1") (pinfunction "+_1") (pintype "passive"))
      (node (ref "R32") (pin "2") (pinfunction "2_2") (pintype "passive"))
    )
    (net (code "32") (name "Net-(DD1-OSC_IN{slash}PD0)") (class "Default")
      (node (ref "DD1") (pin "2") (pinfunction "OSC_IN/PD0_2") (pintype "input"))
      (node (ref "Y1") (pin "1") (pinfunction "1_1") (pintype "passive"))
    )
    (net (code "33") (name "Net-(DD1-OSC_OUT{slash}PD1)") (class "Default")
      (node (ref "DD1") (pin "3") (pinfunction "OSC_OUT/PD1_3") (pintype "output"))
      (node (ref "Y1") (pin "3") (pinfunction "3_3") (pintype "passive"))
    )
    (net (code "34") (name "Net-(DD1-PA15{slash}JTDI)") (class "Default")
      (node (ref "DD1") (pin "29") (pinfunction "PA15/JTDI_29") (pintype "bidirectional"))
      (node (ref "R15") (pin "2") (pinfunction "2_2") (pintype "passive"))
    )
    (net (code "35") (name "Net-(DD1-PB6)") (class "Default")
      (node (ref "DD1") (pin "33") (pinfunction "PB6_33") (pintype "bidirectional"))
      (node (ref "R10") (pin "2") (pinfunction "2_2") (pintype "passive"))
    )
    (net (code "36") (name "Net-(DD1-PB7)") (class "Default")
      (node (ref "DD1") (pin "34") (pinfunction "PB7_34") (pintype "bidirectional"))
      (node (ref "R11") (pin "2") (pinfunction "2_2") (pintype "passive"))
    )
    (net (code "37") (name "Net-(LED1-A)") (class "Default")
      (node (ref "LED1") (pin "1") (pinfunction "A_1") (pintype "passive"))
      (node (ref "R1") (pin "1") (pinfunction "1_1") (pintype "passive"))
    )
    (net (code "38") (name "Net-(LED2-K)") (class "Default")
      (node (ref "LED2") (pin "2") (pinfunction "K_2") (pintype "passive"))
      (node (ref "LED3") (pin "1") (pinfunction "A_1") (pintype "passive"))
      (node (ref "R17") (pin "2") (pinfunction "2_2") (pintype "passive"))
    )
    (net (code "39") (name "Net-(P2-Pad1)") (class "Default")
      (node (ref "P2") (pin "1") (pinfunction "1_1") (pintype "passive"))
      (node (ref "R27") (pin "1") (pinfunction "1_1") (pintype "passive"))
    )
    (net (code "40") (name "Net-(P2-Pad5)") (class "Default")
      (node (ref "P2") (pin "5") (pinfunction "5_5") (pintype "passive"))
      (node (ref "R33") (pin "1") (pinfunction "1_1") (pintype "passive"))
    )
    (net (code "41") (name "Net-(R12-Pad1)") (class "Default")
      (node (ref "R12") (pin "1") (pinfunction "1_1") (pintype "passive"))
      (node (ref "R13") (pin "1") (pinfunction "1_1") (pintype "passive"))
      (node (ref "R14") (pin "1") (pinfunction "1_1") (pintype "passive"))
      (node (ref "R16") (pin "1") (pinfunction "1_1") (pintype "passive"))
      (node (ref "R18") (pin "1") (pinfunction "1_1") (pintype "passive"))
    )
    (net (code "42") (name "Net-(U2-RT{slash}SYNC)") (class "Default")
      (node (ref "R6") (pin "2") (pinfunction "2_2") (pintype "passive"))
      (node (ref "U2") (pin "4") (pinfunction "RT/SYNC_4") (pintype "input"))
    )
    (net (code "43") (name "Net-(U3-PH)") (class "Default")
      (node (ref "R23") (pin "1") (pinfunction "1_1") (pintype "passive"))
      (node (ref "U3") (pin "1") (pinfunction "PH_1") (pintype "input"))
    )
    (net (code "44") (name "Net-(U3-PWM)") (class "Default")
      (node (ref "R24") (pin "1") (pinfunction "1_1") (pintype "passive"))
      (node (ref "U3") (pin "2") (pinfunction "PWM_2") (pintype "input"))
    )
    (net (code "45") (name "Net-(U3-TOFF)") (class "Default")
      (node (ref "R32") (pin "1") (pinfunction "1_1") (pintype "passive"))
      (node (ref "R34") (pin "1") (pinfunction "1_1") (pintype "passive"))
      (node (ref "U3") (pin "12") (pinfunction "TOFF_12") (pintype "input"))
    )
    (net (code "46") (name "VCC") (class "Default")
      (node (ref "C19") (pin "1") (pintype "passive"))
      (node (ref "C20") (pin "1") (pinfunction "+_1") (pintype "passive"))
      (node (ref "C6") (pin "2") (pinfunction "-_2") (pintype "passive"))
      (node (ref "C7") (pin "1") (pinfunction "+_1") (pintype "passive"))
      (node (ref "J1") (pin "2") (pinfunction "2_2") (pintype "passive"))
      (node (ref "L1") (pin "1") (pinfunction "1_1") (pintype "passive"))
      (node (ref "R3") (pin "2") (pinfunction "2_2") (pintype "passive"))
      (node (ref "R4") (pin "2") (pinfunction "2_2") (pintype "passive"))
      (node (ref "U1") (pin "1") (pinfunction "VIN_1") (pintype "power_in"))
      (node (ref "U3") (pin "6") (pinfunction "VS_6") (pintype "power_in"))
    )
    (net (code "47") (name "unconnected-(DD1-PA3-Pad10)") (class "Default")
      (node (ref "DD1") (pin "10") (pinfunction "PA3_10") (pintype "bidirectional"))
    )
    (net (code "48") (name "unconnected-(DD1-PA4-Pad11)") (class "Default")
      (node (ref "DD1") (pin "11") (pinfunction "PA4_11") (pintype "bidirectional"))
    )
    (net (code "49") (name "unconnected-(DD1-PA5-Pad12)") (class "Default")
      (node (ref "DD1") (pin "12") (pinfunction "PA5_12") (pintype "bidirectional"))
    )
    (net (code "50") (name "unconnected-(DD1-PA6-Pad13)") (class "Default")
      (node (ref "DD1") (pin "13") (pinfunction "PA6_13") (pintype "bidirectional"))
    )
    (net (code "51") (name "unconnected-(DD1-PA7-Pad14)") (class "Default")
      (node (ref "DD1") (pin "14") (pinfunction "PA7_14") (pintype "bidirectional"))
    )
    (net (code "52") (name "unconnected-(DD1-PA10-Pad22)") (class "Default")
      (node (ref "DD1") (pin "22") (pinfunction "PA10_22") (pintype "bidirectional"))
    )
    (net (code "53") (name "unconnected-(DD1-PA11-Pad23)") (class "Default")
      (node (ref "DD1") (pin "23") (pinfunction "PA11_23") (pintype "bidirectional"))
    )
    (net (code "54") (name "unconnected-(DD1-PA12-Pad24)") (class "Default")
      (node (ref "DD1") (pin "24") (pinfunction "PA12_24") (pintype "bidirectional"))
    )
    (net (code "55") (name "unconnected-(DD1-PB0-Pad15)") (class "Default")
      (node (ref "DD1") (pin "15") (pinfunction "PB0_15") (pintype "bidirectional"))
    )
    (net (code "56") (name "unconnected-(DD1-PB1-Pad16)") (class "Default")
      (node (ref "DD1") (pin "16") (pinfunction "PB1_16") (pintype "bidirectional"))
    )
    (net (code "57") (name "unconnected-(SWD1-SHIELD-PadS1)") (class "Default")
      (node (ref "SWD1") (pin "S1") (pinfunction "SHIELD_S1") (pintype "passive"))
    )
    (net (code "58") (name "unconnected-(SWD1-SHIELD-PadS2)") (class "Default")
      (node (ref "SWD1") (pin "S2") (pinfunction "SHIELD_S2") (pintype "passive"))
    )
    (net (code "59") (name "unconnected-(U1-EN-Pad3)") (class "Default")
      (node (ref "U1") (pin "3") (pinfunction "EN_3") (pintype "input"))
    )
    (net (code "60") (name "unconnected-(U2-EN-Pad3)") (class "Default")
      (node (ref "U2") (pin "3") (pinfunction "EN_3") (pintype "input"))
    )
  )
)
